# H26R01.net
KiCad netlist of a schematic drawn in EAGLE
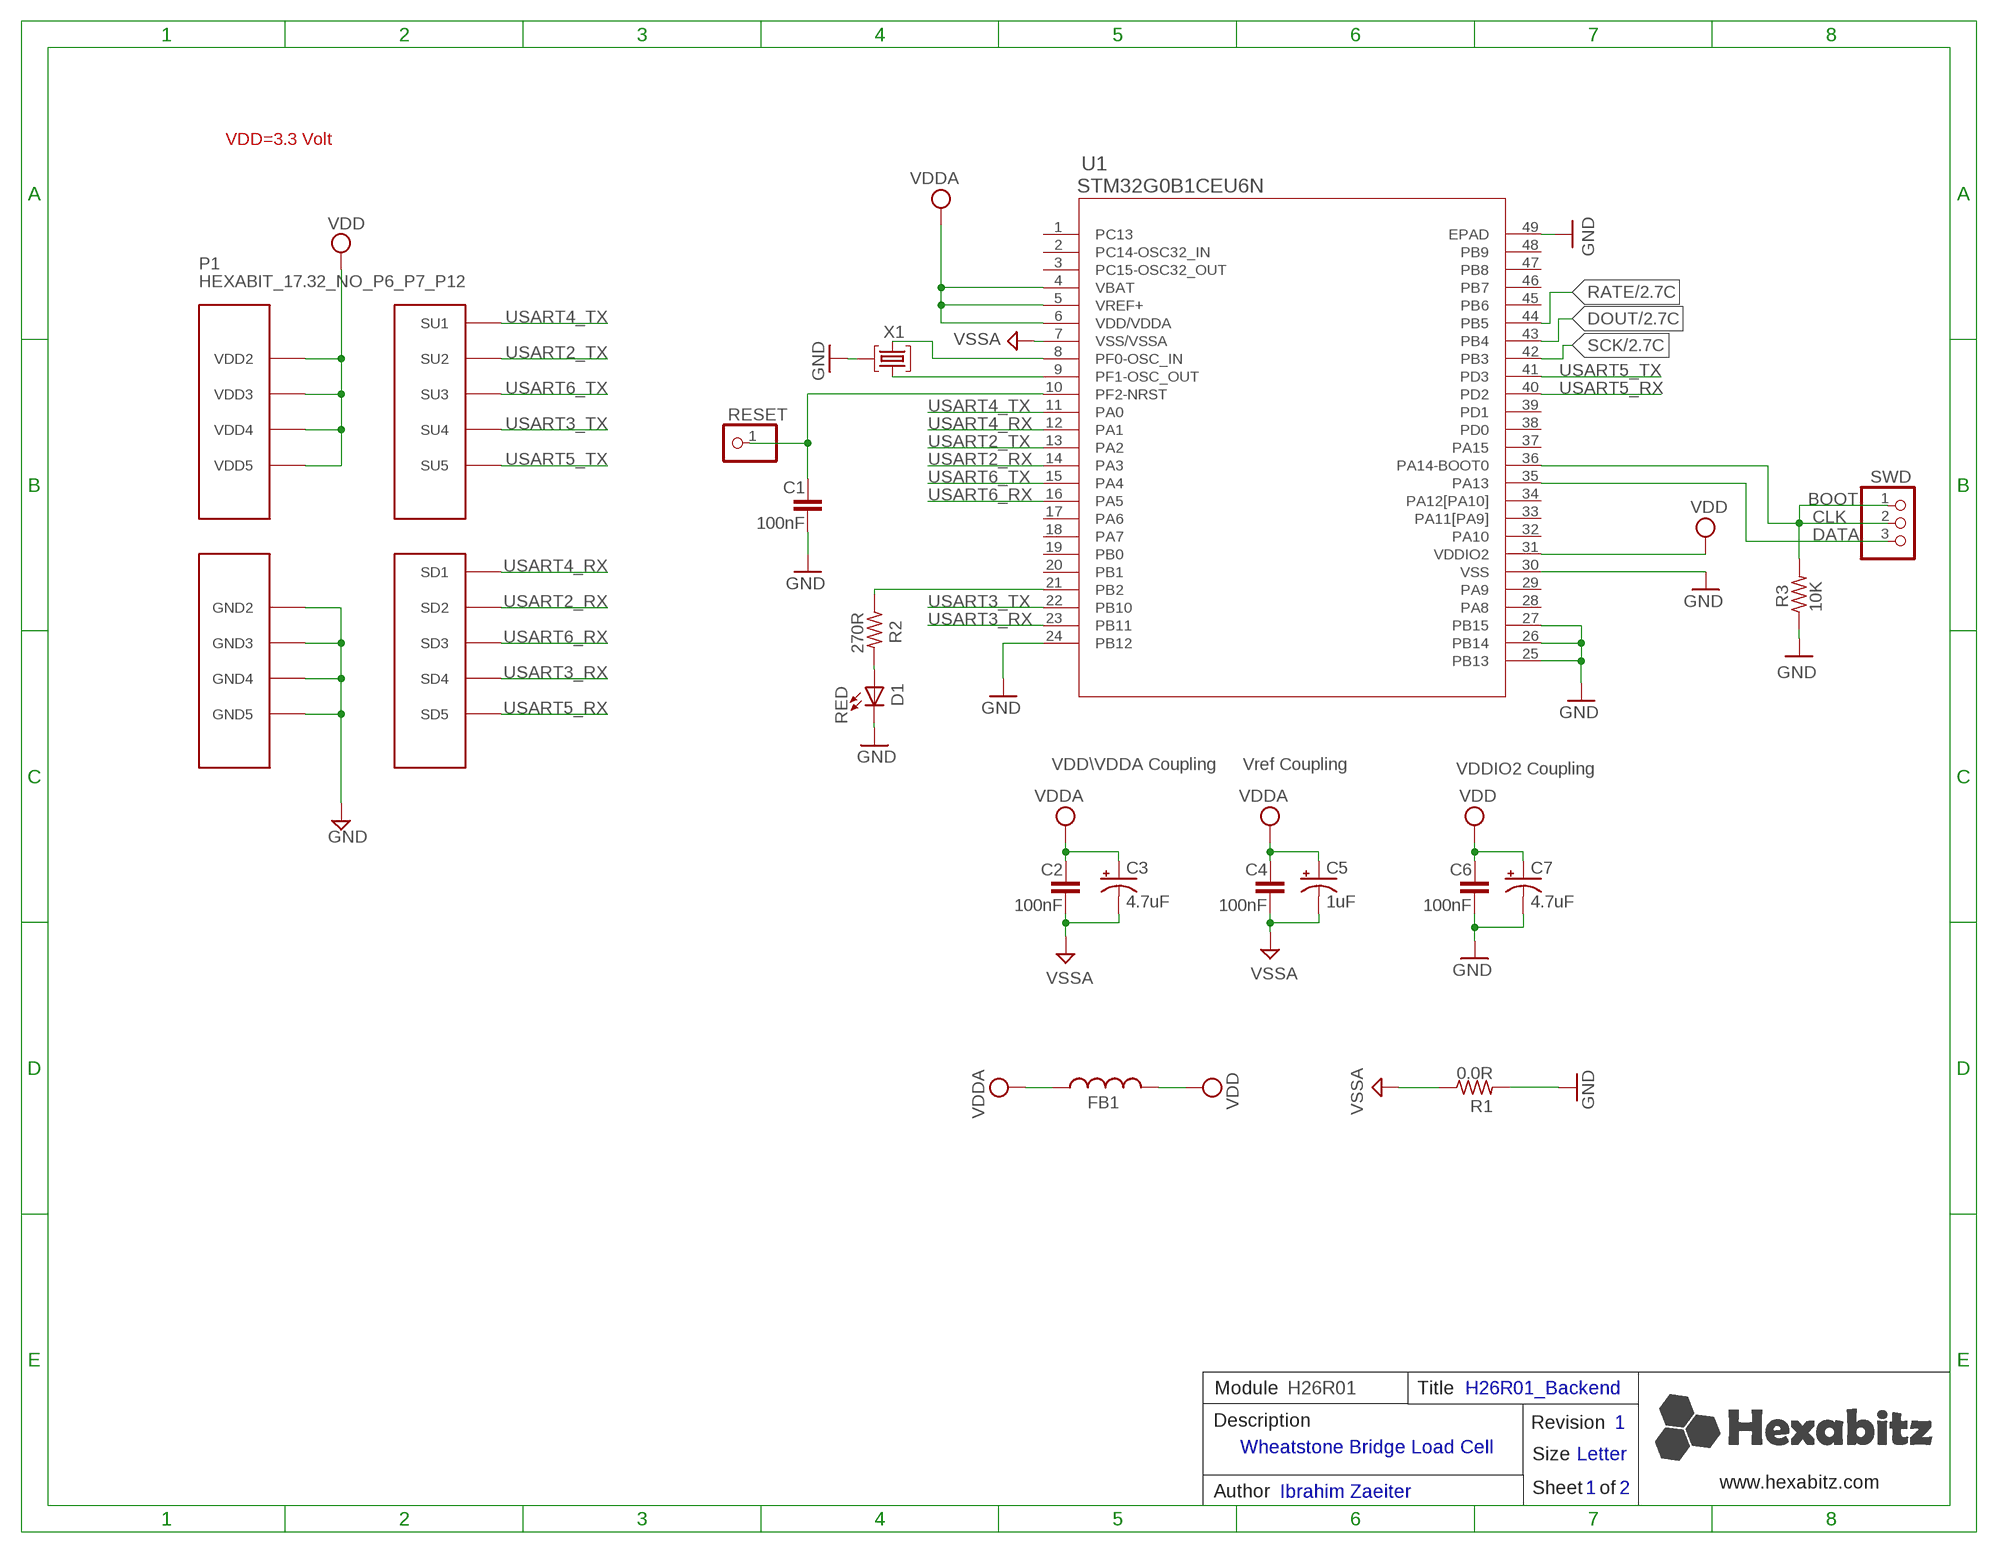
[diagram p0: schematic, sheet 1]
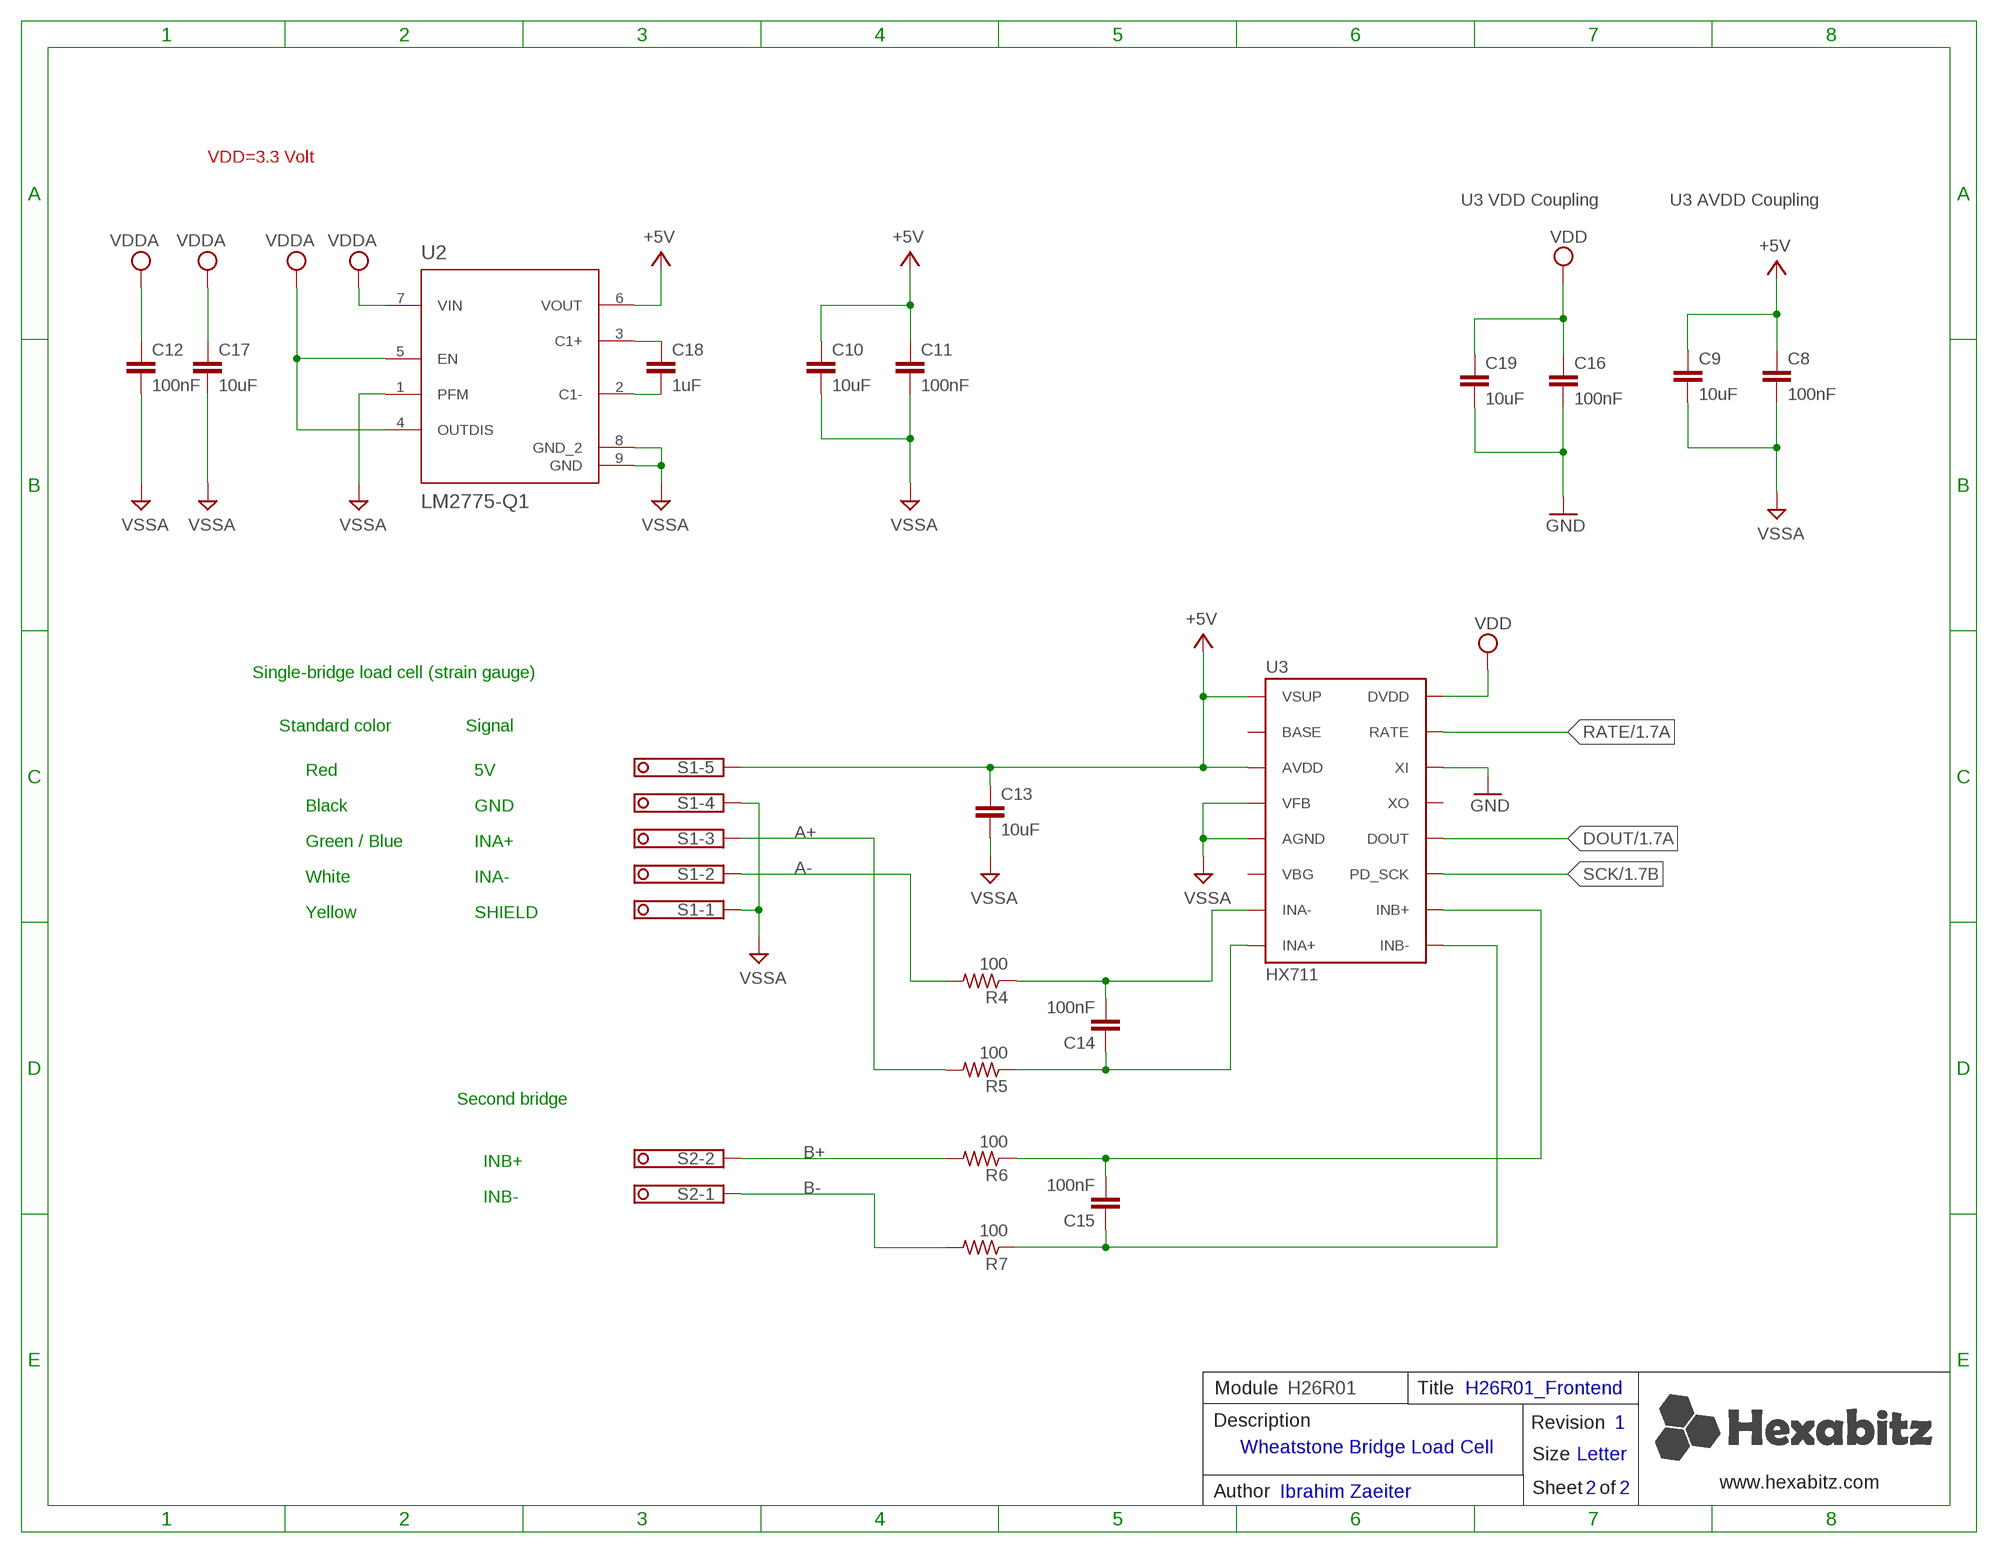
[diagram p1: schematic, sheet 2]

(export (version "E")
  (design (tool "Eeschema 10.0.6"))
  (components
    (comp (ref "C8")
      (value "100nF")
      (footprint "eagle-import:C-0603")
      (fields
        (field (name "CAPACITANCE") "100nF")
        (field (name "MFN") "KEMET")
        (field (name "MPN") "C0603C104K8RACTU")
        (field (name "OCTOPART_URL") "https://octopart.com/c0603c104k8ractu-kemet-145075?r=sp&s=9bS9ASSwSEqMCE9KBEQZ0g")
        (field (name "TOLERANCE") "10%")
        (field (name "VOLTAGE_RATING") "10V")
      )
      (libsource (lib "eagle-import") (part "C-0603"))
    )
    (comp (ref "C9")
      (value "10uF")
      (footprint "eagle-import:C-0603")
      (fields
        (field (name "CAPACITANCE") "10uF")
        (field (name "MFN") "Murarta")
        (field (name "MPN") "GRM188R61A106KE69D")
        (field (name "OCTOPART_URL") "https://octopart.com/grm188r61a106ke69d-murata-22851381?r=ap&s=o9t4ILLiSny6rfdd0oM5Kg")
        (field (name "TOLERANCE") "10%")
        (field (name "VOLTAGE_RATING") "10V")
      )
      (libsource (lib "eagle-import") (part "C-0603"))
    )
    (comp (ref "C10")
      (value "10uF")
      (footprint "eagle-import:C-0603")
      (fields
        (field (name "CAPACITANCE") "10uF")
        (field (name "MFN") "Murarta")
        (field (name "MPN") "GRM188R61A106KE69D")
        (field (name "OCTOPART_URL") "https://octopart.com/grm188r61a106ke69d-murata-22851381?r=ap&s=o9t4ILLiSny6rfdd0oM5Kg")
        (field (name "TOLERANCE") "10%")
        (field (name "VOLTAGE_RATING") "10V")
      )
      (libsource (lib "eagle-import") (part "C-0603"))
    )
    (comp (ref "C11")
      (value "100nF")
      (footprint "eagle-import:C-0603")
      (fields
        (field (name "CAPACITANCE") "100nF")
        (field (name "MFN") "KEMET")
        (field (name "MPN") "C0603C104K8RACTU")
        (field (name "OCTOPART_URL") "https://octopart.com/c0603c104k8ractu-kemet-145075?r=sp&s=9bS9ASSwSEqMCE9KBEQZ0g")
        (field (name "TOLERANCE") "10%")
        (field (name "VOLTAGE_RATING") "10V")
      )
      (libsource (lib "eagle-import") (part "C-0603"))
    )
    (comp (ref "C12")
      (value "100nF")
      (footprint "eagle-import:C-0603")
      (fields
        (field (name "CAPACITANCE") "100nF")
        (field (name "MFN") "KEMET")
        (field (name "MPN") "C0603C104K8RACTU")
        (field (name "OCTOPART_URL") "https://octopart.com/c0603c104k8ractu-kemet-145075?r=sp&s=9bS9ASSwSEqMCE9KBEQZ0g")
        (field (name "TOLERANCE") "10%")
        (field (name "VOLTAGE_RATING") "10V")
      )
      (libsource (lib "eagle-import") (part "C-0603"))
    )
    (comp (ref "C13")
      (value "10uF")
      (footprint "eagle-import:C-0603")
      (fields
        (field (name "CAPACITANCE") "10uF")
        (field (name "MFN") "Murata")
        (field (name "MPN") "GRM188R61A106KE69D")
        (field (name "OCTOPART_URL") "https://octopart.com/grm188r61a106ke69d-murata-22851381?r=ap&s=o9t4ILLiSny6rfdd0oM5Kg")
        (field (name "TOLERANCE") "10%")
        (field (name "VOLTAGE_RATING") "10V")
      )
      (libsource (lib "eagle-import") (part "C-0603"))
    )
    (comp (ref "C14")
      (value "100nF")
      (footprint "eagle-import:C-0603")
      (fields
        (field (name "CAPACITANCE") "100nF")
        (field (name "MFN") "KEMET")
        (field (name "MPN") "C0603C104K8RACTU")
        (field (name "OCTOPART_URL") "https://octopart.com/c0603c104k8ractu-kemet-145075?r=sp&s=9bS9ASSwSEqMCE9KBEQZ0g")
        (field (name "TOLERANCE") "10V")
        (field (name "VOLTAGE_RATING") "10%")
      )
      (libsource (lib "eagle-import") (part "C-0603"))
    )
    (comp (ref "C15")
      (value "100nF")
      (footprint "eagle-import:C-0603")
      (fields
        (field (name "CAPACITANCE") "100nF")
        (field (name "MFN") "KEMET")
        (field (name "MPN") "C0603C104K8RACTU")
        (field (name "OCTOPART_URL") "https://octopart.com/c0603c104k8ractu-kemet-145075?r=sp&s=9bS9ASSwSEqMCE9KBEQZ0g")
        (field (name "TOLERANCE") "10V")
        (field (name "VOLTAGE_RATING") "10%")
      )
      (libsource (lib "eagle-import") (part "C-0603"))
    )
    (comp (ref "C16")
      (value "100nF")
      (footprint "eagle-import:C-0603")
      (fields
        (field (name "CAPACITANCE") "100nF")
        (field (name "MFN") "KEMET")
        (field (name "MPN") "C0603C104K8RACTU")
        (field (name "OCTOPART_URL") "https://octopart.com/c0603c104k8ractu-kemet-145075?r=sp&s=9bS9ASSwSEqMCE9KBEQZ0g")
        (field (name "TOLERANCE") "10%")
        (field (name "VOLTAGE_RATING") "10V")
      )
      (libsource (lib "eagle-import") (part "C-0603"))
    )
    (comp (ref "C17")
      (value "10uF")
      (footprint "eagle-import:C-0603")
      (fields
        (field (name "CAPACITANCE") "10uF")
        (field (name "MFN") "Murarta")
        (field (name "MPN") "GRM188R61A106KE69D")
        (field (name "OCTOPART_URL") "https://octopart.com/grm188r61a106ke69d-murata-22851381?r=ap&s=o9t4ILLiSny6rfdd0oM5Kg")
        (field (name "TOLERANCE") "10%")
        (field (name "VOLTAGE_RATING") "10V")
      )
      (libsource (lib "eagle-import") (part "C-0603"))
    )
    (comp (ref "C18")
      (value "1uF")
      (footprint "eagle-import:C-0603")
      (fields
        (field (name "CAPACITANCE") "1uF")
        (field (name "MFN") "Murarta")
        (field (name "MPN") "GRM188R61A105KA61J")
        (field (name "OCTOPART_URL") "https://octopart.com/grm188r61a105ka61j-murata-9221870?r=sp&s=wvtiDxTpS1CkWsFaa2pliQ")
        (field (name "TOLERANCE") "10%")
        (field (name "VOLTAGE_RATING") "10V")
      )
      (libsource (lib "eagle-import") (part "C-0603"))
    )
    (comp (ref "C19")
      (value "10uF")
      (footprint "eagle-import:C-0603")
      (fields
        (field (name "CAPACITANCE") "10uF")
        (field (name "MFN") "Murarta")
        (field (name "MPN") "GRM188R61A106KE69D")
        (field (name "OCTOPART_URL") "https://octopart.com/grm188r61a106ke69d-murata-22851381?r=ap&s=o9t4ILLiSny6rfdd0oM5Kg")
        (field (name "TOLERANCE") "10%")
        (field (name "VOLTAGE_RATING") "10V")
      )
      (libsource (lib "eagle-import") (part "C-0603"))
    )
    (comp (ref "R4")
      (value "100")
      (footprint "eagle-import:R-0603")
      (fields
        (field (name "MFN") "Yageo")
        (field (name "MPN") "RC0603JR-07100RL")
        (field (name "OCTOPART_URL") "https://octopart.com/rc0603jr-07100rl-yageo-55458504?r=sp&s=j3XfnGiETZqzM9npqpV08Q")
        (field (name "RESISTANCE") "100")
        (field (name "TOLERANCE") "5%")
      )
      (libsource (lib "eagle-import") (part "R-0603"))
    )
    (comp (ref "R5")
      (value "100")
      (footprint "eagle-import:R-0603")
      (fields
        (field (name "MFN") "Yageo")
        (field (name "MPN") "RC0603JR-07100RL")
        (field (name "OCTOPART_URL") "https://octopart.com/rc0603jr-07100rl-yageo-55458504?r=sp&s=j3XfnGiETZqzM9npqpV08Q")
        (field (name "RESISTANCE") "100")
        (field (name "TOLERANCE") "5%")
      )
      (libsource (lib "eagle-import") (part "R-0603"))
    )
    (comp (ref "R6")
      (value "100")
      (footprint "eagle-import:R-0603")
      (fields
        (field (name "MFN") "Yageo")
        (field (name "MPN") "RC0603JR-07100RL")
        (field (name "OCTOPART_URL") "https://octopart.com/rc0603jr-07100rl-yageo-55458504?r=sp&s=j3XfnGiETZqzM9npqpV08Q")
        (field (name "RESISTANCE") "100")
        (field (name "TOLERANCE") "5%")
      )
      (libsource (lib "eagle-import") (part "R-0603"))
    )
    (comp (ref "R7")
      (value "100")
      (footprint "eagle-import:R-0603")
      (fields
        (field (name "MFN") "Yageo")
        (field (name "MPN") "RC0603JR-07100RL")
        (field (name "OCTOPART_URL") "https://octopart.com/rc0603jr-07100rl-yageo-55458504?r=sp&s=j3XfnGiETZqzM9npqpV08Q")
        (field (name "RESISTANCE") "100")
        (field (name "TOLERANCE") "5%")
      )
      (libsource (lib "eagle-import") (part "R-0603"))
    )
    (comp (ref "S1")
      (value "CON-PHOENIX-350_1751277")
      (footprint "eagle-import:CON-PHOENIX-350_1751277")
      (fields
        (field (name "MPN") "1984646")
        (field (name "MFN") "Phoenix Contact")
        (field (name "OCTOPART_URL") "https://octopart.com/1984646-phoenix+contact-50274?r=sp&s=drI_GVM4QHaL48lSCATrxQ")
      )
      (libsource (lib "eagle-import") (part "CON-PHOENIX-350_1751277"))
    )
    (comp (ref "S2")
      (value "CON-PHOENIX-350_1751248")
      (footprint "eagle-import:CON-PHOENIX-350_1751248")
      (fields
        (field (name "MPN") "1751251")
        (field (name "MFN") "Phoenix Contact")
        (field (name "MPN_1") "1984617")
        (field (name "OCTOPART_URL") "https://octopart.com/1984617-phoenix+contact-58834?r=sp&s=Ef_UaV1JSFmY0wggQyN1Mw")
      )
      (libsource (lib "eagle-import") (part "CON-PHOENIX-350_1751248"))
    )
    (comp (ref "U2")
      (value "LM2775-Q1")
      (footprint "eagle-import:DSG0008A")
      (fields (field (name "MANUFACTURER") "Texas Instruments") (field (name "MPN") "LM2775QDSGRQ1"))
      (libsource (lib "eagle-import") (part "LM2775QDSGRQ1"))
    )
    (comp (ref "U3")
      (value "HX711")
      (footprint "eagle-import:HX711_SO16")
      (fields (field (name "MFN") "Avia Semiconductor") (field (name "MPN") "HX711"))
      (libsource (lib "eagle-import") (part "HX711"))
    )
    (comp (ref "C1")
      (value "100nF")
      (footprint "eagle-import:C-0603")
      (libsource (lib "eagle-import") (part "C-0603"))
    )
    (comp (ref "C2")
      (value "100nF")
      (footprint "eagle-import:C-0603")
      (libsource (lib "eagle-import") (part "C-0603"))
    )
    (comp (ref "C3")
      (value "4.7uF")
      (footprint "eagle-import:C-0805-POL")
      (libsource (lib "eagle-import") (part "C-0805-POL"))
    )
    (comp (ref "C4")
      (value "100nF")
      (footprint "eagle-import:C-0603")
      (libsource (lib "eagle-import") (part "C-0603"))
    )
    (comp (ref "C5")
      (value "1uF")
      (footprint "eagle-import:C-0805-POL")
      (libsource (lib "eagle-import") (part "C-0805-POL"))
    )
    (comp (ref "C6")
      (value "100nF")
      (footprint "eagle-import:C-0603")
      (libsource (lib "eagle-import") (part "C-0603"))
    )
    (comp (ref "C7")
      (value "4.7uF")
      (footprint "eagle-import:C-0805-POL")
      (libsource (lib "eagle-import") (part "C-0805-POL"))
    )
    (comp (ref "D1")
      (value "RED")
      (footprint "eagle-import:VLMS1300-GS08")
      (fields
        (field (name "MPN") "VLMS1300-GS08")
        (field (name "MFN") "Vishay")
        (field (name "MPN_1") "VLMS1300-GS08")
        (field (name "OCTOPART_URL") "https://octopart.com/vlms1300-gs08-vishay-21709201?r=sp&s=_gcP4_q8T1SC6PJQPTQ9yA")
      )
      (libsource (lib "eagle-import") (part "VLMS1300-GS08"))
    )
    (comp (ref "FB1")
      (value "FB-0603")
      (footprint "eagle-import:FB-0603")
      (libsource (lib "eagle-import") (part "FB-0603"))
    )
    (comp (ref "P1")
      (value "HEXABIT_17.32_NO_P6_P7_P12")
      (footprint "eagle-import:HEXABIT_17.32_NO_P6_P7_P12")
      (libsource (lib "eagle-import") (part "HEXABIT_?_NO_P6_P7_P1217.32"))
    )
    (comp (ref "R1")
      (value "0.0R")
      (footprint "eagle-import:R-0603")
      (libsource (lib "eagle-import") (part "R-0603"))
    )
    (comp (ref "R2")
      (value "270R")
      (footprint "eagle-import:R-0603")
      (libsource (lib "eagle-import") (part "R-0603"))
    )
    (comp (ref "R3")
      (value "10K")
      (footprint "eagle-import:R-0603")
      (libsource (lib "eagle-import") (part "R-0603"))
    )
    (comp (ref "RESET")
      (value "R")
      (footprint "eagle-import:1X01")
      (fields (field (name "MPN") "87227-1"))
      (libsource (lib "eagle-import") (part "PINHD-1X1"))
    )
    (comp (ref "SWD")
      (value "PINHD-1X3")
      (footprint "eagle-import:1X03")
      (libsource (lib "eagle-import") (part "PINHD-1X3"))
    )
    (comp (ref "U1")
      (value "STM32G0B1CEU6N")
      (footprint "eagle-import:HEXABITZ_ICS_QFN_B1CEU6_STM-L")
      (libsource (lib "eagle-import") (part "STM32G0B1CEU6N"))
    )
    (comp (ref "X1")
      (value "XTALL_CSTCE8M00G52")
      (footprint "eagle-import:XTALL_CSTCE8M00G52")
      (fields (field (name "MPN") "CSTCE8M00G52Z-R0"))
      (libsource (lib "eagle-import") (part "XTALL_CSTCE8M00G52"))
    )
  )
  (nets
    (net (code "1") (name "+5V") (class "Default")
      (node (ref "C10") (pin "1") (pinfunction "1_1") (pintype "passive"))
      (node (ref "C11") (pin "1") (pinfunction "1_1") (pintype "passive"))
      (node (ref "C13") (pin "1") (pinfunction "1_1") (pintype "passive"))
      (node (ref "C8") (pin "1") (pinfunction "1_1") (pintype "passive"))
      (node (ref "C9") (pin "1") (pinfunction "1_1") (pintype "passive"))
      (node (ref "S1") (pin "5") (pinfunction "K_5") (pintype "passive"))
      (node (ref "U2") (pin "6") (pinfunction "VOUT_6") (pintype "power_in"))
      (node (ref "U3") (pin "1") (pinfunction "VSUP_1") (pintype "bidirectional"))
      (node (ref "U3") (pin "3") (pinfunction "AVDD_3") (pintype "bidirectional"))
    )
    (net (code "2") (name "A+") (class "Default")
      (node (ref "R5") (pin "2") (pinfunction "2_2") (pintype "passive"))
      (node (ref "S1") (pin "3") (pinfunction "K_3") (pintype "passive"))
    )
    (net (code "3") (name "A-") (class "Default")
      (node (ref "R4") (pin "2") (pinfunction "2_2") (pintype "passive"))
      (node (ref "S1") (pin "2") (pinfunction "K_2") (pintype "passive"))
    )
    (net (code "4") (name "B+") (class "Default")
      (node (ref "R6") (pin "2") (pinfunction "2_2") (pintype "passive"))
      (node (ref "S2") (pin "2") (pinfunction "K_2") (pintype "passive"))
    )
    (net (code "5") (name "B-") (class "Default")
      (node (ref "R7") (pin "2") (pinfunction "2_2") (pintype "passive"))
      (node (ref "S2") (pin "1") (pinfunction "K_1") (pintype "passive"))
    )
    (net (code "6") (name "CLK") (class "Default")
      (node (ref "R3") (pin "2") (pinfunction "2_2") (pintype "passive"))
      (node (ref "SWD") (pin "1") (pinfunction "1_1") (pintype "passive"))
      (node (ref "SWD") (pin "2") (pinfunction "2_2") (pintype "passive"))
      (node (ref "U1") (pin "36") (pinfunction "PA14-BOOT0_36") (pintype "bidirectional"))
    )
    (net (code "7") (name "DATA") (class "Default")
      (node (ref "SWD") (pin "3") (pinfunction "3_3") (pintype "passive"))
      (node (ref "U1") (pin "35") (pinfunction "PA13_35") (pintype "bidirectional"))
    )
    (net (code "8") (name "DOUT") (class "Default")
      (node (ref "U1") (pin "43") (pinfunction "PB4_43") (pintype "bidirectional"))
      (node (ref "U3") (pin "12") (pinfunction "DOUT_12") (pintype "bidirectional"))
    )
    (net (code "9") (name "GND") (class "Default")
      (node (ref "C1") (pin "2") (pinfunction "2_2") (pintype "passive"))
      (node (ref "C16") (pin "2") (pinfunction "2_2") (pintype "passive"))
      (node (ref "C19") (pin "2") (pinfunction "2_2") (pintype "passive"))
      (node (ref "C6") (pin "2") (pinfunction "2_2") (pintype "passive"))
      (node (ref "C7") (pin "2") (pinfunction "-_2") (pintype "passive"))
      (node (ref "D1") (pin "C") (pinfunction "C_C") (pintype "passive"))
      (node (ref "P1") (pin "PAD_PD10") (pinfunction "GND4_PAD_PD10") (pintype "power_in"))
      (node (ref "P1") (pin "PAD_PD11") (pinfunction "GND5_PAD_PD11") (pintype "power_in"))
      (node (ref "P1") (pin "PAD_PD8") (pinfunction "GND2_PAD_PD8") (pintype "power_in"))
      (node (ref "P1") (pin "PAD_PD9") (pinfunction "GND3_PAD_PD9") (pintype "power_in"))
      (node (ref "R1") (pin "2") (pinfunction "2_2") (pintype "passive"))
      (node (ref "R3") (pin "1") (pinfunction "1_1") (pintype "passive"))
      (node (ref "U1") (pin "24") (pinfunction "PB12_24") (pintype "bidirectional"))
      (node (ref "U1") (pin "25") (pinfunction "PB13_25") (pintype "bidirectional"))
      (node (ref "U1") (pin "26") (pinfunction "PB14_26") (pintype "bidirectional"))
      (node (ref "U1") (pin "27") (pinfunction "PB15_27") (pintype "bidirectional"))
      (node (ref "U1") (pin "30") (pinfunction "VSS_30") (pintype "passive"))
      (node (ref "U1") (pin "49") (pinfunction "EPAD_49") (pintype "passive"))
      (node (ref "U3") (pin "14") (pinfunction "XI_14") (pintype "bidirectional"))
      (node (ref "X1") (pin "P$2") (pinfunction "2_P$2") (pintype "passive"))
    )
    (net (code "10") (name "Net-(D1-PadA)") (class "Default")
      (node (ref "D1") (pin "A") (pinfunction "A_A") (pintype "passive"))
      (node (ref "R2") (pin "2") (pinfunction "2_2") (pintype "passive"))
    )
    (net (code "11") (name "Net-(U1-PB2)") (class "Default")
      (node (ref "R2") (pin "1") (pinfunction "1_1") (pintype "passive"))
      (node (ref "U1") (pin "21") (pinfunction "PB2_21") (pintype "bidirectional"))
    )
    (net (code "12") (name "Net-(U1-PF0-OSC_IN)") (class "Default")
      (node (ref "U1") (pin "8") (pinfunction "PF0-OSC_IN_8") (pintype "bidirectional"))
      (node (ref "X1") (pin "P$3") (pinfunction "3_P$3") (pintype "passive"))
    )
    (net (code "13") (name "Net-(U1-PF1-OSC_OUT)") (class "Default")
      (node (ref "U1") (pin "9") (pinfunction "PF1-OSC_OUT_9") (pintype "bidirectional"))
      (node (ref "X1") (pin "P$1") (pinfunction "1_P$1") (pintype "passive"))
    )
    (net (code "14") (name "Net-(U1-PF2-NRST)") (class "Default")
      (node (ref "C1") (pin "1") (pinfunction "1_1") (pintype "passive"))
      (node (ref "RESET") (pin "1") (pinfunction "1_1") (pintype "passive"))
      (node (ref "U1") (pin "10") (pinfunction "PF2-NRST_10") (pintype "bidirectional"))
    )
    (net (code "15") (name "Net-(U2-C1+)") (class "Default")
      (node (ref "C18") (pin "1") (pinfunction "1_1") (pintype "passive"))
      (node (ref "U2") (pin "3") (pinfunction "C1+_3") (pintype "power_in"))
    )
    (net (code "16") (name "Net-(U2-C1-)") (class "Default")
      (node (ref "C18") (pin "2") (pinfunction "2_2") (pintype "passive"))
      (node (ref "U2") (pin "2") (pinfunction "C1-_2") (pintype "power_in"))
    )
    (net (code "17") (name "Net-(U3-INA+)") (class "Default")
      (node (ref "C14") (pin "1") (pinfunction "1_1") (pintype "passive"))
      (node (ref "R5") (pin "1") (pinfunction "1_1") (pintype "passive"))
      (node (ref "U3") (pin "8") (pinfunction "INA+_8") (pintype "bidirectional"))
    )
    (net (code "18") (name "Net-(U3-INA-)") (class "Default")
      (node (ref "C14") (pin "2") (pinfunction "2_2") (pintype "passive"))
      (node (ref "R4") (pin "1") (pinfunction "1_1") (pintype "passive"))
      (node (ref "U3") (pin "7") (pinfunction "INA-_7") (pintype "bidirectional"))
    )
    (net (code "19") (name "Net-(U3-INB+)") (class "Default")
      (node (ref "C15") (pin "2") (pinfunction "2_2") (pintype "passive"))
      (node (ref "R6") (pin "1") (pinfunction "1_1") (pintype "passive"))
      (node (ref "U3") (pin "10") (pinfunction "INB+_10") (pintype "bidirectional"))
    )
    (net (code "20") (name "Net-(U3-INB-)") (class "Default")
      (node (ref "C15") (pin "1") (pinfunction "1_1") (pintype "passive"))
      (node (ref "R7") (pin "1") (pinfunction "1_1") (pintype "passive"))
      (node (ref "U3") (pin "9") (pinfunction "INB-_9") (pintype "bidirectional"))
    )
    (net (code "21") (name "RATE") (class "Default")
      (node (ref "U1") (pin "44") (pinfunction "PB5_44") (pintype "bidirectional"))
      (node (ref "U3") (pin "15") (pinfunction "RATE_15") (pintype "bidirectional"))
    )
    (net (code "22") (name "SCK") (class "Default")
      (node (ref "U1") (pin "42") (pinfunction "PB3_42") (pintype "bidirectional"))
      (node (ref "U3") (pin "11") (pinfunction "PD_SCK_11") (pintype "bidirectional"))
    )
    (net (code "23") (name "USART2_RX") (class "Default")
      (node (ref "P1") (pin "PAD_PD2") (pinfunction "SD2_PAD_PD2") (pintype "bidirectional"))
      (node (ref "U1") (pin "14") (pinfunction "PA3_14") (pintype "bidirectional"))
    )
    (net (code "24") (name "USART2_TX") (class "Default")
      (node (ref "P1") (pin "PAD_PU2") (pinfunction "SU2_PAD_PU2") (pintype "bidirectional"))
      (node (ref "U1") (pin "13") (pinfunction "PA2_13") (pintype "bidirectional"))
    )
    (net (code "25") (name "USART3_RX") (class "Default")
      (node (ref "P1") (pin "PAD_PD4") (pinfunction "SD4_PAD_PD4") (pintype "bidirectional"))
      (node (ref "U1") (pin "23") (pinfunction "PB11_23") (pintype "bidirectional"))
    )
    (net (code "26") (name "USART3_TX") (class "Default")
      (node (ref "P1") (pin "PAD_PU4") (pinfunction "SU4_PAD_PU4") (pintype "bidirectional"))
      (node (ref "U1") (pin "22") (pinfunction "PB10_22") (pintype "bidirectional"))
    )
    (net (code "27") (name "USART4_RX") (class "Default")
      (node (ref "P1") (pin "PAD_PD1") (pinfunction "SD1_PAD_PD1") (pintype "bidirectional"))
      (node (ref "U1") (pin "12") (pinfunction "PA1_12") (pintype "bidirectional"))
    )
    (net (code "28") (name "USART4_TX") (class "Default")
      (node (ref "P1") (pin "PAD_PU1") (pinfunction "SU1_PAD_PU1") (pintype "bidirectional"))
      (node (ref "U1") (pin "11") (pinfunction "PA0_11") (pintype "bidirectional"))
    )
    (net (code "29") (name "USART5_RX") (class "Default")
      (node (ref "P1") (pin "PAD_PD5") (pinfunction "SD5_PAD_PD5") (pintype "bidirectional"))
      (node (ref "U1") (pin "40") (pinfunction "PD2_40") (pintype "bidirectional"))
    )
    (net (code "30") (name "USART5_TX") (class "Default")
      (node (ref "P1") (pin "PAD_PU5") (pinfunction "SU5_PAD_PU5") (pintype "bidirectional"))
      (node (ref "U1") (pin "41") (pinfunction "PD3_41") (pintype "bidirectional"))
    )
    (net (code "31") (name "USART6_RX") (class "Default")
      (node (ref "P1") (pin "PAD_PD3") (pinfunction "SD3_PAD_PD3") (pintype "bidirectional"))
      (node (ref "U1") (pin "16") (pinfunction "PA5_16") (pintype "bidirectional"))
    )
    (net (code "32") (name "USART6_TX") (class "Default")
      (node (ref "P1") (pin "PAD_PU3") (pinfunction "SU3_PAD_PU3") (pintype "bidirectional"))
      (node (ref "U1") (pin "15") (pinfunction "PA4_15") (pintype "bidirectional"))
    )
    (net (code "33") (name "VDD") (class "Default")
      (node (ref "C16") (pin "1") (pinfunction "1_1") (pintype "passive"))
      (node (ref "C19") (pin "1") (pinfunction "1_1") (pintype "passive"))
      (node (ref "C6") (pin "1") (pinfunction "1_1") (pintype "passive"))
      (node (ref "C7") (pin "1") (pinfunction "+_1") (pintype "passive"))
      (node (ref "FB1") (pin "2") (pinfunction "2_2") (pintype "passive"))
      (node (ref "P1") (pin "PAD_PU10") (pinfunction "VDD4_PAD_PU10") (pintype "power_in"))
      (node (ref "P1") (pin "PAD_PU11") (pinfunction "VDD5_PAD_PU11") (pintype "power_in"))
      (node (ref "P1") (pin "PAD_PU8") (pinfunction "VDD2_PAD_PU8") (pintype "power_in"))
      (node (ref "P1") (pin "PAD_PU9") (pinfunction "VDD3_PAD_PU9") (pintype "power_in"))
      (node (ref "U1") (pin "31") (pinfunction "VDDIO2_31") (pintype "power_in"))
      (node (ref "U3") (pin "16") (pinfunction "DVDD_16") (pintype "bidirectional"))
    )
    (net (code "34") (name "VDDA") (class "Default")
      (node (ref "C12") (pin "1") (pinfunction "1_1") (pintype "passive"))
      (node (ref "C17") (pin "1") (pinfunction "1_1") (pintype "passive"))
      (node (ref "C2") (pin "1") (pinfunction "1_1") (pintype "passive"))
      (node (ref "C3") (pin "1") (pinfunction "+_1") (pintype "passive"))
      (node (ref "C4") (pin "1") (pinfunction "1_1") (pintype "passive"))
      (node (ref "C5") (pin "1") (pinfunction "+_1") (pintype "passive"))
      (node (ref "FB1") (pin "1") (pinfunction "1_1") (pintype "passive"))
      (node (ref "U1") (pin "4") (pinfunction "VBAT_4") (pintype "power_in"))
      (node (ref "U1") (pin "5") (pinfunction "VREF+_5") (pintype "power_in"))
      (node (ref "U1") (pin "6") (pinfunction "VDD/VDDA_6") (pintype "power_in"))
      (node (ref "U2") (pin "4") (pinfunction "OUTDIS_4") (pintype "input"))
      (node (ref "U2") (pin "5") (pinfunction "EN_5") (pintype "input"))
      (node (ref "U2") (pin "7") (pinfunction "VIN_7") (pintype "power_in"))
    )
    (net (code "35") (name "VSSA") (class "Default")
      (node (ref "C10") (pin "2") (pinfunction "2_2") (pintype "passive"))
      (node (ref "C11") (pin "2") (pinfunction "2_2") (pintype "passive"))
      (node (ref "C12") (pin "2") (pinfunction "2_2") (pintype "passive"))
      (node (ref "C13") (pin "2") (pinfunction "2_2") (pintype "passive"))
      (node (ref "C17") (pin "2") (pinfunction "2_2") (pintype "passive"))
      (node (ref "C2") (pin "2") (pinfunction "2_2") (pintype "passive"))
      (node (ref "C3") (pin "2") (pinfunction "-_2") (pintype "passive"))
      (node (ref "C4") (pin "2") (pinfunction "2_2") (pintype "passive"))
      (node (ref "C5") (pin "2") (pinfunction "-_2") (pintype "passive"))
      (node (ref "C8") (pin "2") (pinfunction "2_2") (pintype "passive"))
      (node (ref "C9") (pin "2") (pinfunction "2_2") (pintype "passive"))
      (node (ref "R1") (pin "1") (pinfunction "1_1") (pintype "passive"))
      (node (ref "S1") (pin "1") (pinfunction "K_1") (pintype "passive"))
      (node (ref "S1") (pin "4") (pinfunction "K_4") (pintype "passive"))
      (node (ref "U1") (pin "7") (pinfunction "VSS/VSSA_7") (pintype "passive"))
      (node (ref "U2") (pin "1") (pinfunction "PFM_1") (pintype "input"))
      (node (ref "U2") (pin "8") (pinfunction "GND_2_8") (pintype "power_in"))
      (node (ref "U2") (pin "9") (pinfunction "GND_9") (pintype "power_in"))
      (node (ref "U3") (pin "4") (pinfunction "VFB_4") (pintype "bidirectional"))
      (node (ref "U3") (pin "5") (pinfunction "AGND_5") (pintype "bidirectional"))
    )
    (net (code "36") (name "unconnected-(U1-PA6-Pad17)") (class "Default")
      (node (ref "U1") (pin "17") (pinfunction "PA6_17") (pintype "bidirectional"))
    )
    (net (code "37") (name "unconnected-(U1-PA7-Pad18)") (class "Default")
      (node (ref "U1") (pin "18") (pinfunction "PA7_18") (pintype "bidirectional"))
    )
    (net (code "38") (name "unconnected-(U1-PA8-Pad28)") (class "Default")
      (node (ref "U1") (pin "28") (pinfunction "PA8_28") (pintype "bidirectional"))
    )
    (net (code "39") (name "unconnected-(U1-PA9-Pad29)") (class "Default")
      (node (ref "U1") (pin "29") (pinfunction "PA9_29") (pintype "bidirectional"))
    )
    (net (code "40") (name "unconnected-(U1-PA10-Pad32)") (class "Default")
      (node (ref "U1") (pin "32") (pinfunction "PA10_32") (pintype "bidirectional"))
    )
    (net (code "41") (name "unconnected-(U1-PA11[PA9]-Pad33)") (class "Default")
      (node (ref "U1") (pin "33") (pinfunction "PA11[PA9]_33") (pintype "bidirectional"))
    )
    (net (code "42") (name "unconnected-(U1-PA12[PA10]-Pad34)") (class "Default")
      (node (ref "U1") (pin "34") (pinfunction "PA12[PA10]_34") (pintype "bidirectional"))
    )
    (net (code "43") (name "unconnected-(U1-PA15-Pad37)") (class "Default")
      (node (ref "U1") (pin "37") (pinfunction "PA15_37") (pintype "bidirectional"))
    )
    (net (code "44") (name "unconnected-(U1-PB0-Pad19)") (class "Default")
      (node (ref "U1") (pin "19") (pinfunction "PB0_19") (pintype "bidirectional"))
    )
    (net (code "45") (name "unconnected-(U1-PB1-Pad20)") (class "Default")
      (node (ref "U1") (pin "20") (pinfunction "PB1_20") (pintype "bidirectional"))
    )
    (net (code "46") (name "unconnected-(U1-PB6-Pad45)") (class "Default")
      (node (ref "U1") (pin "45") (pinfunction "PB6_45") (pintype "bidirectional"))
    )
    (net (code "47") (name "unconnected-(U1-PB7-Pad46)") (class "Default")
      (node (ref "U1") (pin "46") (pinfunction "PB7_46") (pintype "bidirectional"))
    )
    (net (code "48") (name "unconnected-(U1-PB8-Pad47)") (class "Default")
      (node (ref "U1") (pin "47") (pinfunction "PB8_47") (pintype "bidirectional"))
    )
    (net (code "49") (name "unconnected-(U1-PB9-Pad48)") (class "Default")
      (node (ref "U1") (pin "48") (pinfunction "PB9_48") (pintype "bidirectional"))
    )
    (net (code "50") (name "unconnected-(U1-PC13-Pad1)") (class "Default")
      (node (ref "U1") (pin "1") (pinfunction "PC13_1") (pintype "bidirectional"))
    )
    (net (code "51") (name "unconnected-(U1-PC14-OSC32_IN-Pad2)") (class "Default")
      (node (ref "U1") (pin "2") (pinfunction "PC14-OSC32_IN_2") (pintype "bidirectional"))
    )
    (net (code "52") (name "unconnected-(U1-PC15-OSC32_OUT-Pad3)") (class "Default")
      (node (ref "U1") (pin "3") (pinfunction "PC15-OSC32_OUT_3") (pintype "bidirectional"))
    )
    (net (code "53") (name "unconnected-(U1-PD0-Pad38)") (class "Default")
      (node (ref "U1") (pin "38") (pinfunction "PD0_38") (pintype "bidirectional"))
    )
    (net (code "54") (name "unconnected-(U1-PD1-Pad39)") (class "Default")
      (node (ref "U1") (pin "39") (pinfunction "PD1_39") (pintype "bidirectional"))
    )
    (net (code "55") (name "unconnected-(U3-BASE-Pad2)") (class "Default")
      (node (ref "U3") (pin "2") (pinfunction "BASE_2") (pintype "bidirectional"))
    )
    (net (code "56") (name "unconnected-(U3-VBG-Pad6)") (class "Default")
      (node (ref "U3") (pin "6") (pinfunction "VBG_6") (pintype "bidirectional"))
    )
    (net (code "57") (name "unconnected-(U3-XO-Pad13)") (class "Default")
      (node (ref "U3") (pin "13") (pinfunction "XO_13") (pintype "bidirectional"))
    )
  )
)
